# akilli_olcum_cihazi.net
KiCad netlist of a schematic drawn in EAGLE
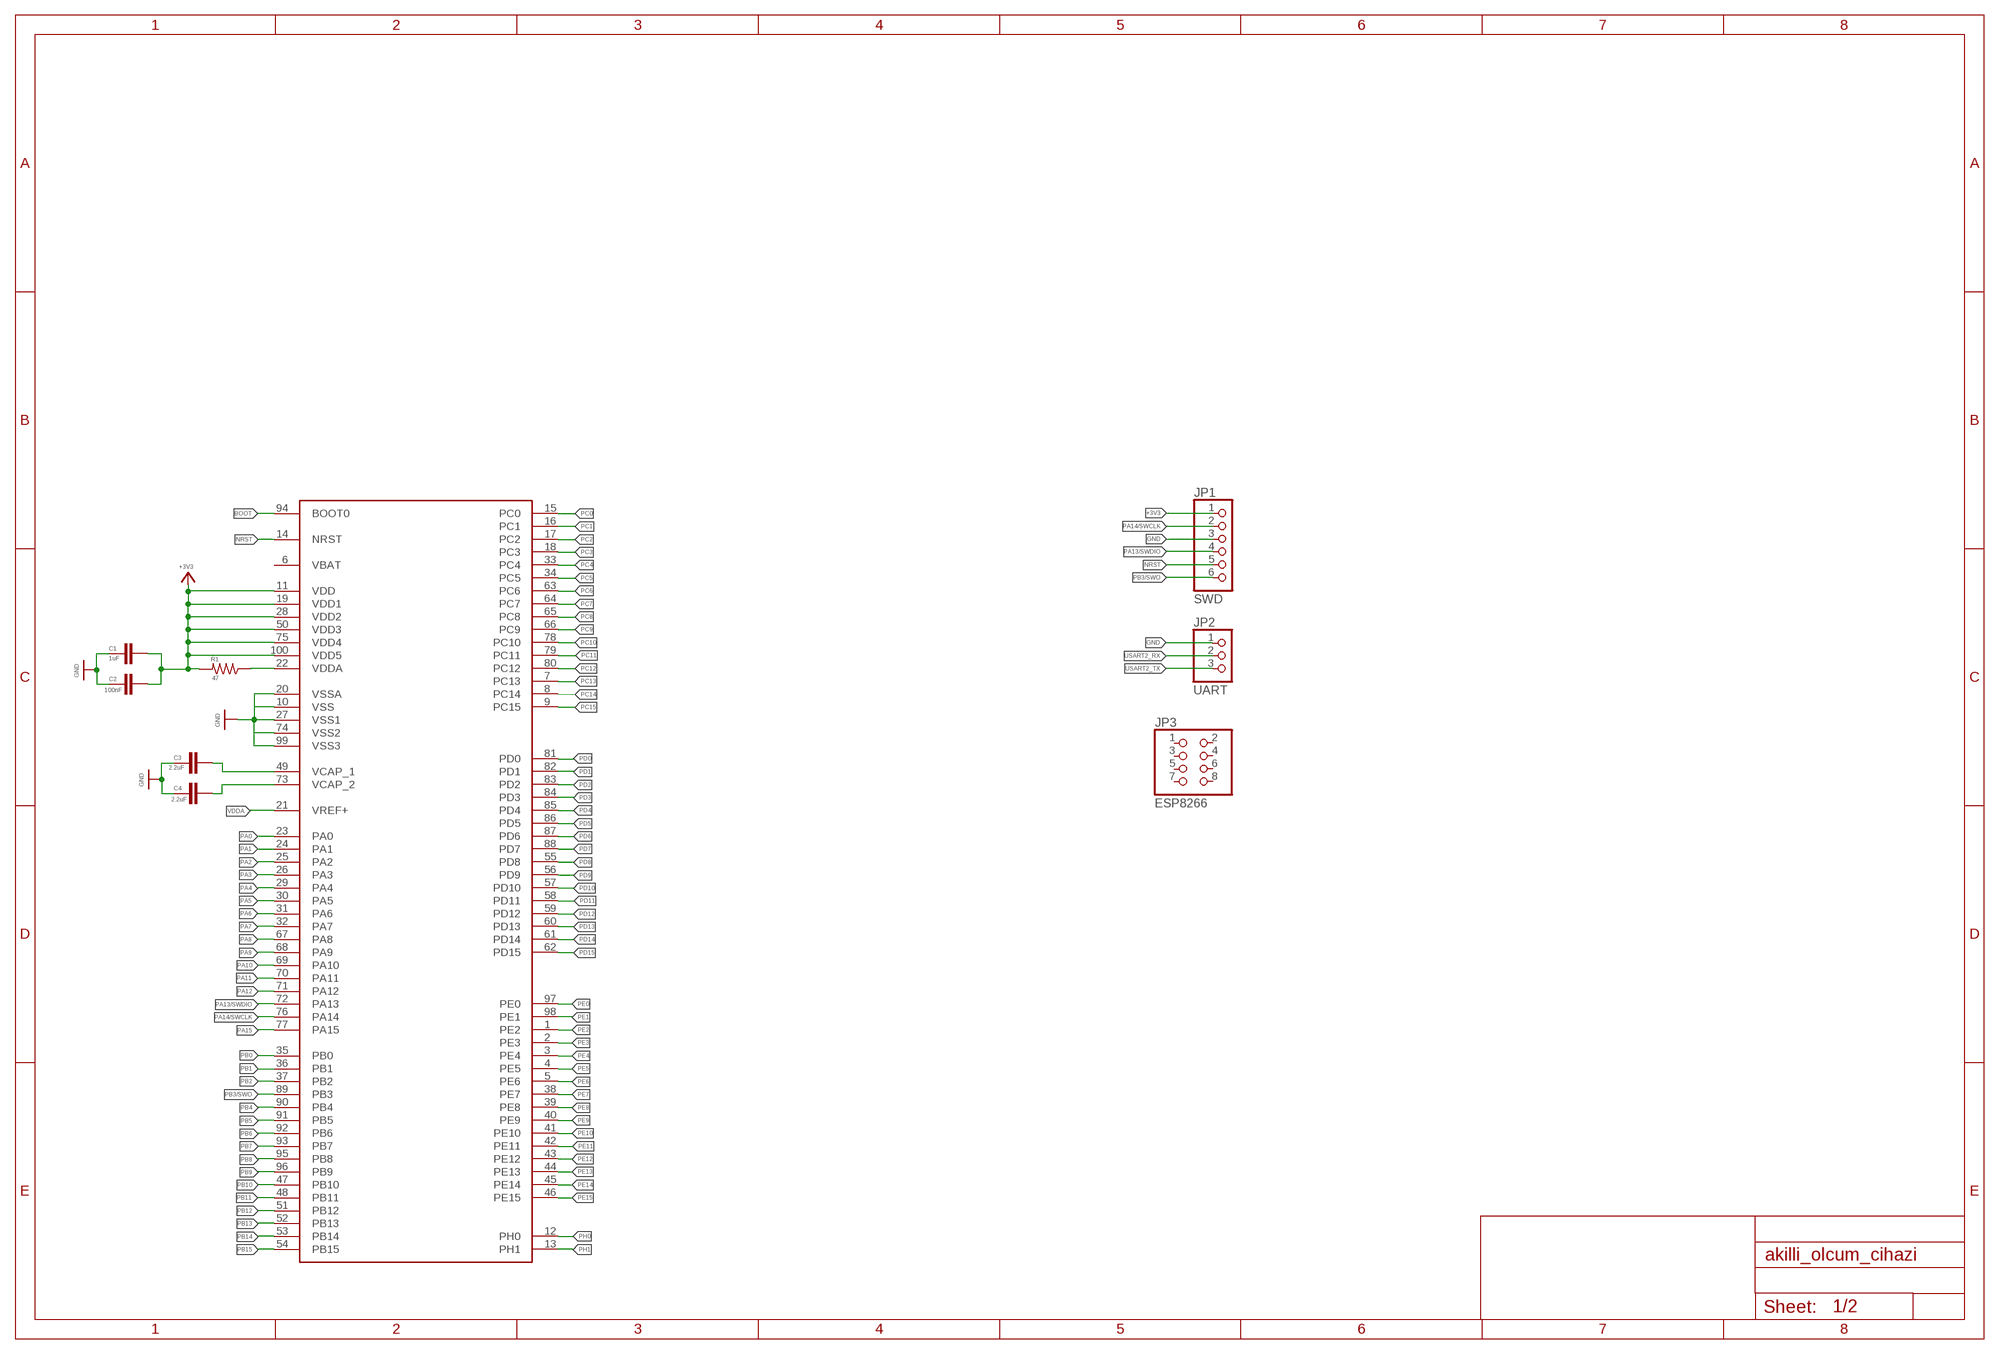
[diagram p0: schematic, sheet 1]
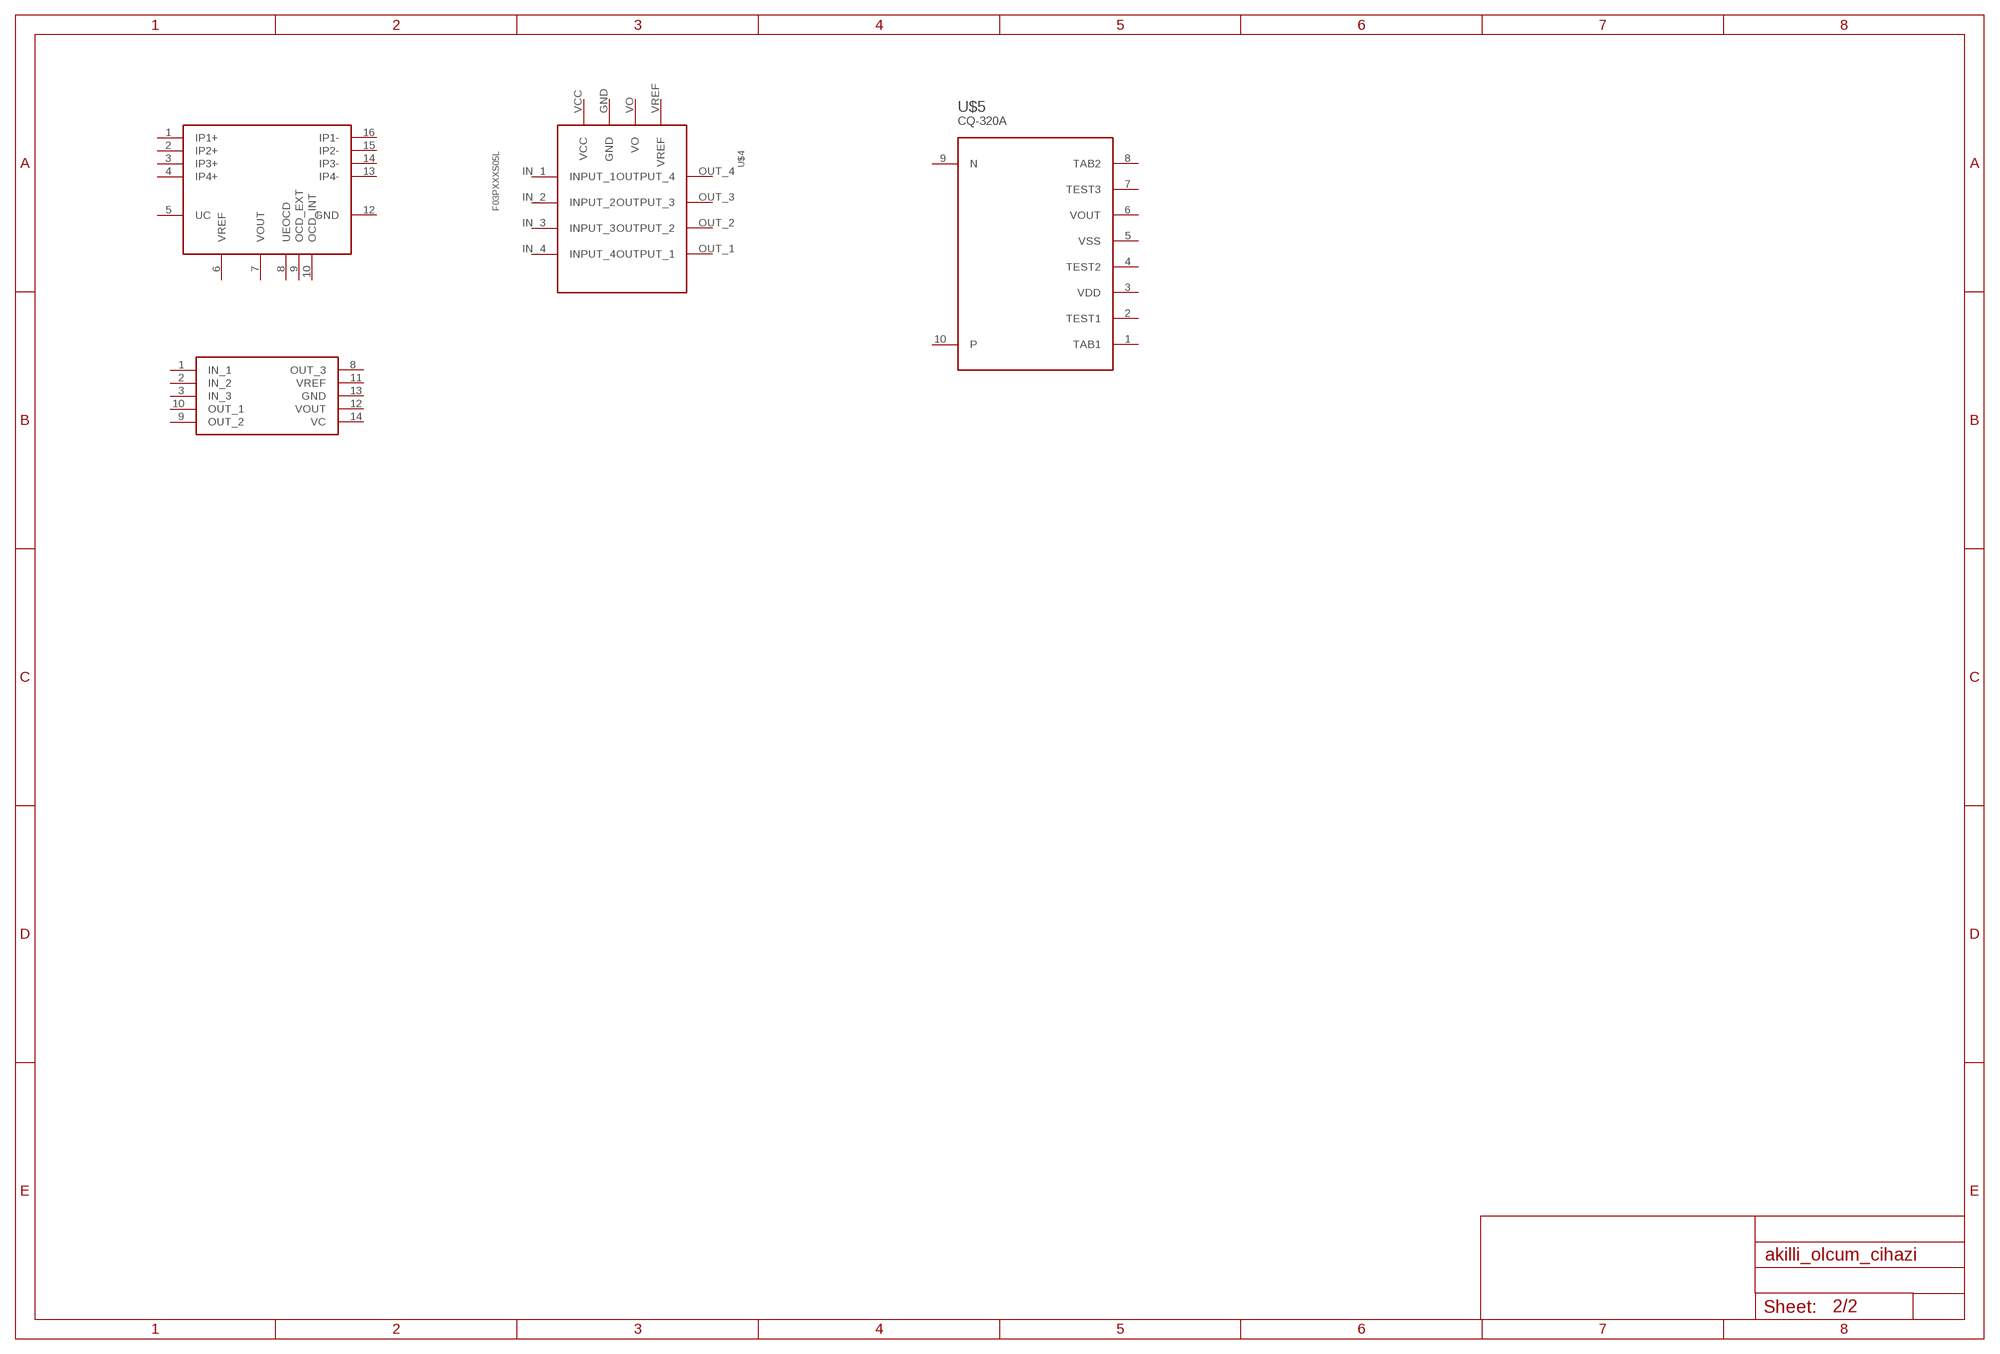
[diagram p1: schematic, sheet 2]

(export (version "E")
  (design (tool "Eeschema 10.0.6"))
  (components
    (comp (ref "C1")
      (value "1uF")
      (footprint "eagle-import:C0805")
      (libsource (lib "eagle-import") (part "C"))
    )
    (comp (ref "C2")
      (value "100nF")
      (footprint "eagle-import:C0805")
      (libsource (lib "eagle-import") (part "C"))
    )
    (comp (ref "C3")
      (value "2.2uF")
      (footprint "eagle-import:C0805")
      (libsource (lib "eagle-import") (part "C"))
    )
    (comp (ref "C4")
      (value "2.2uF")
      (footprint "eagle-import:C0805")
      (libsource (lib "eagle-import") (part "C"))
    )
    (comp (ref "JP1")
      (value "SWD")
      (footprint "eagle-import:1X06")
      (libsource (lib "eagle-import") (part "PINHD-1X6"))
    )
    (comp (ref "JP2")
      (value "UART")
      (footprint "eagle-import:1X03")
      (libsource (lib "eagle-import") (part "PINHD-1X3"))
    )
    (comp (ref "JP3")
      (value "ESP8266")
      (footprint "eagle-import:2X04")
      (libsource (lib "eagle-import") (part "PINHD-2X4"))
    )
    (comp (ref "R1")
      (value "47")
      (footprint "eagle-import:R1206")
      (libsource (lib "eagle-import") (part "R-US_R1206"))
    )
    (comp (ref "U$1")
      (value "STM32F40XSTM32D40X")
      (footprint "eagle-import:LQFP100")
      (libsource (lib "eagle-import") (part "STM32F40XSTM32D40X"))
    )
    (comp (ref "U$2")
      (value "LEM_G02")
      (footprint "eagle-import:LEM_G02")
      (libsource (lib "eagle-import") (part "LEM_G02"))
    )
    (comp (ref "U$3")
      (value "LEM_CASR")
      (footprint "eagle-import:LEM")
      (libsource (lib "eagle-import") (part "LEM_CASR"))
    )
    (comp (ref "U$4")
      (value "F03PXXXS05L")
      (footprint "eagle-import:F03PXXXS05L")
      (libsource (lib "eagle-import") (part "F03PXXXS05L"))
    )
    (comp (ref "U$5")
      (value "CQ-320A")
      (footprint "eagle-import:CQ-320A")
      (libsource (lib "eagle-import") (part "CQ-320A"))
    )
  )
  (nets
    (net (code "1") (name "+3V3") (class "Default")
      (node (ref "C1") (pin "2") (pinfunction "2_2") (pintype "passive"))
      (node (ref "C2") (pin "2") (pinfunction "2_2") (pintype "passive"))
      (node (ref "JP1") (pin "1") (pinfunction "1_1") (pintype "passive"))
      (node (ref "R1") (pin "2") (pinfunction "2_2") (pintype "passive"))
      (node (ref "U$1") (pin "100") (pinfunction "VDD5_100") (pintype "bidirectional"))
      (node (ref "U$1") (pin "11") (pinfunction "VDD_11") (pintype "bidirectional"))
      (node (ref "U$1") (pin "19") (pinfunction "VDD1_19") (pintype "bidirectional"))
      (node (ref "U$1") (pin "28") (pinfunction "VDD2_28") (pintype "bidirectional"))
      (node (ref "U$1") (pin "50") (pinfunction "VDD3_50") (pintype "bidirectional"))
      (node (ref "U$1") (pin "75") (pinfunction "VDD4_75") (pintype "bidirectional"))
    )
    (net (code "2") (name "BOOT") (class "Default")
      (node (ref "U$1") (pin "94") (pinfunction "BOOT0_94") (pintype "bidirectional"))
    )
    (net (code "3") (name "GND") (class "Default")
      (node (ref "C1") (pin "1") (pinfunction "1_1") (pintype "passive"))
      (node (ref "C2") (pin "1") (pinfunction "1_1") (pintype "passive"))
      (node (ref "C3") (pin "1") (pinfunction "1_1") (pintype "passive"))
      (node (ref "C4") (pin "1") (pinfunction "1_1") (pintype "passive"))
      (node (ref "JP1") (pin "3") (pinfunction "3_3") (pintype "passive"))
      (node (ref "JP2") (pin "1") (pinfunction "1_1") (pintype "passive"))
      (node (ref "U$1") (pin "10") (pinfunction "VSS_10") (pintype "bidirectional"))
      (node (ref "U$1") (pin "20") (pinfunction "VSSA_20") (pintype "bidirectional"))
      (node (ref "U$1") (pin "27") (pinfunction "VSS1_27") (pintype "bidirectional"))
      (node (ref "U$1") (pin "74") (pinfunction "VSS2_74") (pintype "bidirectional"))
      (node (ref "U$1") (pin "99") (pinfunction "VSS3_99") (pintype "bidirectional"))
    )
    (net (code "4") (name "NRST") (class "Default")
      (node (ref "JP1") (pin "5") (pinfunction "5_5") (pintype "passive"))
      (node (ref "U$1") (pin "14") (pinfunction "NRST_14") (pintype "bidirectional"))
    )
    (net (code "5") (name "Net-(U$1-VCAP_1)") (class "Default")
      (node (ref "C3") (pin "2") (pinfunction "2_2") (pintype "passive"))
      (node (ref "U$1") (pin "49") (pinfunction "VCAP_1_49") (pintype "bidirectional"))
    )
    (net (code "6") (name "Net-(U$1-VCAP_2)") (class "Default")
      (node (ref "C4") (pin "2") (pinfunction "2_2") (pintype "passive"))
      (node (ref "U$1") (pin "73") (pinfunction "VCAP_2_73") (pintype "bidirectional"))
    )
    (net (code "7") (name "PA0") (class "Default")
      (node (ref "U$1") (pin "23") (pinfunction "PA0_23") (pintype "bidirectional"))
    )
    (net (code "8") (name "PA1") (class "Default")
      (node (ref "U$1") (pin "24") (pinfunction "PA1_24") (pintype "bidirectional"))
    )
    (net (code "9") (name "PA2") (class "Default")
      (node (ref "U$1") (pin "25") (pinfunction "PA2_25") (pintype "bidirectional"))
    )
    (net (code "10") (name "PA3") (class "Default")
      (node (ref "U$1") (pin "26") (pinfunction "PA3_26") (pintype "bidirectional"))
    )
    (net (code "11") (name "PA4") (class "Default")
      (node (ref "U$1") (pin "29") (pinfunction "PA4_29") (pintype "bidirectional"))
    )
    (net (code "12") (name "PA5") (class "Default")
      (node (ref "U$1") (pin "30") (pinfunction "PA5_30") (pintype "bidirectional"))
    )
    (net (code "13") (name "PA6") (class "Default")
      (node (ref "U$1") (pin "31") (pinfunction "PA6_31") (pintype "bidirectional"))
    )
    (net (code "14") (name "PA7") (class "Default")
      (node (ref "U$1") (pin "32") (pinfunction "PA7_32") (pintype "bidirectional"))
    )
    (net (code "15") (name "PA8") (class "Default")
      (node (ref "U$1") (pin "67") (pinfunction "PA8_67") (pintype "bidirectional"))
    )
    (net (code "16") (name "PA9") (class "Default")
      (node (ref "U$1") (pin "68") (pinfunction "PA9_68") (pintype "bidirectional"))
    )
    (net (code "17") (name "PA10") (class "Default")
      (node (ref "U$1") (pin "69") (pinfunction "PA10_69") (pintype "bidirectional"))
    )
    (net (code "18") (name "PA11") (class "Default")
      (node (ref "U$1") (pin "70") (pinfunction "PA11_70") (pintype "bidirectional"))
    )
    (net (code "19") (name "PA12") (class "Default")
      (node (ref "U$1") (pin "71") (pinfunction "PA12_71") (pintype "bidirectional"))
    )
    (net (code "20") (name "PA13{slash}SWDIO") (class "Default")
      (node (ref "JP1") (pin "4") (pinfunction "4_4") (pintype "passive"))
      (node (ref "U$1") (pin "72") (pinfunction "PA13_72") (pintype "bidirectional"))
    )
    (net (code "21") (name "PA14{slash}SWCLK") (class "Default")
      (node (ref "JP1") (pin "2") (pinfunction "2_2") (pintype "passive"))
      (node (ref "U$1") (pin "76") (pinfunction "PA14_76") (pintype "bidirectional"))
    )
    (net (code "22") (name "PA15") (class "Default")
      (node (ref "U$1") (pin "77") (pinfunction "PA15_77") (pintype "bidirectional"))
    )
    (net (code "23") (name "PB0") (class "Default")
      (node (ref "U$1") (pin "35") (pinfunction "PB0_35") (pintype "bidirectional"))
    )
    (net (code "24") (name "PB1") (class "Default")
      (node (ref "U$1") (pin "36") (pinfunction "PB1_36") (pintype "bidirectional"))
    )
    (net (code "25") (name "PB2") (class "Default")
      (node (ref "U$1") (pin "37") (pinfunction "PB2_37") (pintype "bidirectional"))
    )
    (net (code "26") (name "PB3{slash}SWO") (class "Default")
      (node (ref "JP1") (pin "6") (pinfunction "6_6") (pintype "passive"))
      (node (ref "U$1") (pin "89") (pinfunction "PB3_89") (pintype "bidirectional"))
    )
    (net (code "27") (name "PB4") (class "Default")
      (node (ref "U$1") (pin "90") (pinfunction "PB4_90") (pintype "bidirectional"))
    )
    (net (code "28") (name "PB5") (class "Default")
      (node (ref "U$1") (pin "91") (pinfunction "PB5_91") (pintype "bidirectional"))
    )
    (net (code "29") (name "PB6") (class "Default")
      (node (ref "U$1") (pin "92") (pinfunction "PB6_92") (pintype "bidirectional"))
    )
    (net (code "30") (name "PB7") (class "Default")
      (node (ref "U$1") (pin "93") (pinfunction "PB7_93") (pintype "bidirectional"))
    )
    (net (code "31") (name "PB8") (class "Default")
      (node (ref "U$1") (pin "95") (pinfunction "PB8_95") (pintype "bidirectional"))
    )
    (net (code "32") (name "PB9") (class "Default")
      (node (ref "U$1") (pin "96") (pinfunction "PB9_96") (pintype "bidirectional"))
    )
    (net (code "33") (name "PB10") (class "Default")
      (node (ref "U$1") (pin "47") (pinfunction "PB10_47") (pintype "bidirectional"))
    )
    (net (code "34") (name "PB11") (class "Default")
      (node (ref "U$1") (pin "48") (pinfunction "PB11_48") (pintype "bidirectional"))
    )
    (net (code "35") (name "PB12") (class "Default")
      (node (ref "U$1") (pin "51") (pinfunction "PB12_51") (pintype "bidirectional"))
    )
    (net (code "36") (name "PB13") (class "Default")
      (node (ref "U$1") (pin "52") (pinfunction "PB13_52") (pintype "bidirectional"))
    )
    (net (code "37") (name "PB14") (class "Default")
      (node (ref "U$1") (pin "53") (pinfunction "PB14_53") (pintype "bidirectional"))
    )
    (net (code "38") (name "PB15") (class "Default")
      (node (ref "U$1") (pin "54") (pinfunction "PB15_54") (pintype "bidirectional"))
    )
    (net (code "39") (name "PC0") (class "Default")
      (node (ref "U$1") (pin "15") (pinfunction "PC0_15") (pintype "bidirectional"))
    )
    (net (code "40") (name "PC1") (class "Default")
      (node (ref "U$1") (pin "16") (pinfunction "PC1_16") (pintype "bidirectional"))
    )
    (net (code "41") (name "PC2") (class "Default")
      (node (ref "U$1") (pin "17") (pinfunction "PC2_17") (pintype "bidirectional"))
    )
    (net (code "42") (name "PC3") (class "Default")
      (node (ref "U$1") (pin "18") (pinfunction "PC3_18") (pintype "bidirectional"))
    )
    (net (code "43") (name "PC4") (class "Default")
      (node (ref "U$1") (pin "33") (pinfunction "PC4_33") (pintype "bidirectional"))
    )
    (net (code "44") (name "PC5") (class "Default")
      (node (ref "U$1") (pin "34") (pinfunction "PC5_34") (pintype "bidirectional"))
    )
    (net (code "45") (name "PC6") (class "Default")
      (node (ref "U$1") (pin "63") (pinfunction "PC6_63") (pintype "bidirectional"))
    )
    (net (code "46") (name "PC7") (class "Default")
      (node (ref "U$1") (pin "64") (pinfunction "PC7_64") (pintype "bidirectional"))
    )
    (net (code "47") (name "PC8") (class "Default")
      (node (ref "U$1") (pin "65") (pinfunction "PC8_65") (pintype "bidirectional"))
    )
    (net (code "48") (name "PC9") (class "Default")
      (node (ref "U$1") (pin "66") (pinfunction "PC9_66") (pintype "bidirectional"))
    )
    (net (code "49") (name "PC10") (class "Default")
      (node (ref "U$1") (pin "78") (pinfunction "PC10_78") (pintype "bidirectional"))
    )
    (net (code "50") (name "PC11") (class "Default")
      (node (ref "U$1") (pin "79") (pinfunction "PC11_79") (pintype "bidirectional"))
    )
    (net (code "51") (name "PC12") (class "Default")
      (node (ref "U$1") (pin "80") (pinfunction "PC12_80") (pintype "bidirectional"))
    )
    (net (code "52") (name "PC13") (class "Default")
      (node (ref "U$1") (pin "7") (pinfunction "PC13_7") (pintype "bidirectional"))
    )
    (net (code "53") (name "PC14") (class "Default")
      (node (ref "U$1") (pin "8") (pinfunction "PC14_8") (pintype "bidirectional"))
    )
    (net (code "54") (name "PC15") (class "Default")
      (node (ref "U$1") (pin "9") (pinfunction "PC15_9") (pintype "bidirectional"))
    )
    (net (code "55") (name "PD0") (class "Default")
      (node (ref "U$1") (pin "81") (pinfunction "PD0_81") (pintype "bidirectional"))
    )
    (net (code "56") (name "PD1") (class "Default")
      (node (ref "U$1") (pin "82") (pinfunction "PD1_82") (pintype "bidirectional"))
    )
    (net (code "57") (name "PD2") (class "Default")
      (node (ref "U$1") (pin "83") (pinfunction "PD2_83") (pintype "bidirectional"))
    )
    (net (code "58") (name "PD3") (class "Default")
      (node (ref "U$1") (pin "84") (pinfunction "PD3_84") (pintype "bidirectional"))
    )
    (net (code "59") (name "PD4") (class "Default")
      (node (ref "U$1") (pin "85") (pinfunction "PD4_85") (pintype "bidirectional"))
    )
    (net (code "60") (name "PD5") (class "Default")
      (node (ref "U$1") (pin "86") (pinfunction "PD5_86") (pintype "bidirectional"))
    )
    (net (code "61") (name "PD6") (class "Default")
      (node (ref "U$1") (pin "87") (pinfunction "PD6_87") (pintype "bidirectional"))
    )
    (net (code "62") (name "PD7") (class "Default")
      (node (ref "U$1") (pin "88") (pinfunction "PD7_88") (pintype "bidirectional"))
    )
    (net (code "63") (name "PD8") (class "Default")
      (node (ref "U$1") (pin "55") (pinfunction "PD8_55") (pintype "bidirectional"))
    )
    (net (code "64") (name "PD9") (class "Default")
      (node (ref "U$1") (pin "56") (pinfunction "PD9_56") (pintype "bidirectional"))
    )
    (net (code "65") (name "PD10") (class "Default")
      (node (ref "U$1") (pin "57") (pinfunction "PD10_57") (pintype "bidirectional"))
    )
    (net (code "66") (name "PD11") (class "Default")
      (node (ref "U$1") (pin "58") (pinfunction "PD11_58") (pintype "bidirectional"))
    )
    (net (code "67") (name "PD12") (class "Default")
      (node (ref "U$1") (pin "59") (pinfunction "PD12_59") (pintype "bidirectional"))
    )
    (net (code "68") (name "PD13") (class "Default")
      (node (ref "U$1") (pin "60") (pinfunction "PD13_60") (pintype "bidirectional"))
    )
    (net (code "69") (name "PD14") (class "Default")
      (node (ref "U$1") (pin "61") (pinfunction "PD14_61") (pintype "bidirectional"))
    )
    (net (code "70") (name "PD15") (class "Default")
      (node (ref "U$1") (pin "62") (pinfunction "PD15_62") (pintype "bidirectional"))
    )
    (net (code "71") (name "PE0") (class "Default")
      (node (ref "U$1") (pin "97") (pinfunction "PE0_97") (pintype "bidirectional"))
    )
    (net (code "72") (name "PE1") (class "Default")
      (node (ref "U$1") (pin "98") (pinfunction "PE1_98") (pintype "bidirectional"))
    )
    (net (code "73") (name "PE2") (class "Default")
      (node (ref "U$1") (pin "1") (pinfunction "PE2_1") (pintype "bidirectional"))
    )
    (net (code "74") (name "PE3") (class "Default")
      (node (ref "U$1") (pin "2") (pinfunction "PE3_2") (pintype "bidirectional"))
    )
    (net (code "75") (name "PE4") (class "Default")
      (node (ref "U$1") (pin "3") (pinfunction "PE4_3") (pintype "bidirectional"))
    )
    (net (code "76") (name "PE5") (class "Default")
      (node (ref "U$1") (pin "4") (pinfunction "PE5_4") (pintype "bidirectional"))
    )
    (net (code "77") (name "PE6") (class "Default")
      (node (ref "U$1") (pin "5") (pinfunction "PE6_5") (pintype "bidirectional"))
    )
    (net (code "78") (name "PE7") (class "Default")
      (node (ref "U$1") (pin "38") (pinfunction "PE7_38") (pintype "bidirectional"))
    )
    (net (code "79") (name "PE8") (class "Default")
      (node (ref "U$1") (pin "39") (pinfunction "PE8_39") (pintype "bidirectional"))
    )
    (net (code "80") (name "PE9") (class "Default")
      (node (ref "U$1") (pin "40") (pinfunction "PE9_40") (pintype "bidirectional"))
    )
    (net (code "81") (name "PE10") (class "Default")
      (node (ref "U$1") (pin "41") (pinfunction "PE10_41") (pintype "bidirectional"))
    )
    (net (code "82") (name "PE11") (class "Default")
      (node (ref "U$1") (pin "42") (pinfunction "PE11_42") (pintype "bidirectional"))
    )
    (net (code "83") (name "PE12") (class "Default")
      (node (ref "U$1") (pin "43") (pinfunction "PE12_43") (pintype "bidirectional"))
    )
    (net (code "84") (name "PE13") (class "Default")
      (node (ref "U$1") (pin "44") (pinfunction "PE13_44") (pintype "bidirectional"))
    )
    (net (code "85") (name "PE14") (class "Default")
      (node (ref "U$1") (pin "45") (pinfunction "PE14_45") (pintype "bidirectional"))
    )
    (net (code "86") (name "PE15") (class "Default")
      (node (ref "U$1") (pin "46") (pinfunction "PE15_46") (pintype "bidirectional"))
    )
    (net (code "87") (name "PH0") (class "Default")
      (node (ref "U$1") (pin "12") (pinfunction "PH0_12") (pintype "bidirectional"))
    )
    (net (code "88") (name "PH1") (class "Default")
      (node (ref "U$1") (pin "13") (pinfunction "PH1_13") (pintype "bidirectional"))
    )
    (net (code "89") (name "USART2_RX") (class "Default")
      (node (ref "JP2") (pin "2") (pinfunction "2_2") (pintype "passive"))
    )
    (net (code "90") (name "USART2_TX") (class "Default")
      (node (ref "JP2") (pin "3") (pinfunction "3_3") (pintype "passive"))
    )
    (net (code "91") (name "VDDA") (class "Default")
      (node (ref "R1") (pin "1") (pinfunction "1_1") (pintype "passive"))
      (node (ref "U$1") (pin "21") (pinfunction "VREF+_21") (pintype "bidirectional"))
      (node (ref "U$1") (pin "22") (pinfunction "VDDA_22") (pintype "bidirectional"))
    )
    (net (code "92") (name "unconnected-(JP3-Pad1)") (class "Default")
      (node (ref "JP3") (pin "1") (pinfunction "1_1") (pintype "passive"))
    )
    (net (code "93") (name "unconnected-(JP3-Pad2)") (class "Default")
      (node (ref "JP3") (pin "2") (pinfunction "2_2") (pintype "passive"))
    )
    (net (code "94") (name "unconnected-(JP3-Pad3)") (class "Default")
      (node (ref "JP3") (pin "3") (pinfunction "3_3") (pintype "passive"))
    )
    (net (code "95") (name "unconnected-(JP3-Pad4)") (class "Default")
      (node (ref "JP3") (pin "4") (pinfunction "4_4") (pintype "passive"))
    )
    (net (code "96") (name "unconnected-(JP3-Pad5)") (class "Default")
      (node (ref "JP3") (pin "5") (pinfunction "5_5") (pintype "passive"))
    )
    (net (code "97") (name "unconnected-(JP3-Pad6)") (class "Default")
      (node (ref "JP3") (pin "6") (pinfunction "6_6") (pintype "passive"))
    )
    (net (code "98") (name "unconnected-(JP3-Pad7)") (class "Default")
      (node (ref "JP3") (pin "7") (pinfunction "7_7") (pintype "passive"))
    )
    (net (code "99") (name "unconnected-(JP3-Pad8)") (class "Default")
      (node (ref "JP3") (pin "8") (pinfunction "8_8") (pintype "passive"))
    )
    (net (code "100") (name "unconnected-(U$1-VBAT-Pad6)") (class "Default")
      (node (ref "U$1") (pin "6") (pinfunction "VBAT_6") (pintype "bidirectional"))
    )
    (net (code "101") (name "unconnected-(U$2-GND-Pad12)") (class "Default")
      (node (ref "U$2") (pin "12") (pinfunction "GND_12") (pintype "bidirectional"))
    )
    (net (code "102") (name "unconnected-(U$2-IP1+-Pad1)") (class "Default")
      (node (ref "U$2") (pin "1") (pinfunction "IP1+_1") (pintype "bidirectional"))
    )
    (net (code "103") (name "unconnected-(U$2-IP1--Pad16)") (class "Default")
      (node (ref "U$2") (pin "16") (pinfunction "IP1-_16") (pintype "bidirectional"))
    )
    (net (code "104") (name "unconnected-(U$2-IP2+-Pad2)") (class "Default")
      (node (ref "U$2") (pin "2") (pinfunction "IP2+_2") (pintype "bidirectional"))
    )
    (net (code "105") (name "unconnected-(U$2-IP2--Pad15)") (class "Default")
      (node (ref "U$2") (pin "15") (pinfunction "IP2-_15") (pintype "bidirectional"))
    )
    (net (code "106") (name "unconnected-(U$2-IP3+-Pad3)") (class "Default")
      (node (ref "U$2") (pin "3") (pinfunction "IP3+_3") (pintype "bidirectional"))
    )
    (net (code "107") (name "unconnected-(U$2-IP3--Pad14)") (class "Default")
      (node (ref "U$2") (pin "14") (pinfunction "IP3-_14") (pintype "bidirectional"))
    )
    (net (code "108") (name "unconnected-(U$2-IP4+-Pad4)") (class "Default")
      (node (ref "U$2") (pin "4") (pinfunction "IP4+_4") (pintype "bidirectional"))
    )
    (net (code "109") (name "unconnected-(U$2-IP4--Pad13)") (class "Default")
      (node (ref "U$2") (pin "13") (pinfunction "IP4-_13") (pintype "bidirectional"))
    )
    (net (code "110") (name "unconnected-(U$2-OCD_EXT-Pad9)") (class "Default")
      (node (ref "U$2") (pin "9") (pinfunction "OCD_EXT_9") (pintype "bidirectional"))
    )
    (net (code "111") (name "unconnected-(U$2-OCD_INT-Pad10)") (class "Default")
      (node (ref "U$2") (pin "10") (pinfunction "OCD_INT_10") (pintype "bidirectional"))
    )
    (net (code "112") (name "unconnected-(U$2-UC-Pad5)") (class "Default")
      (node (ref "U$2") (pin "5") (pinfunction "UC_5") (pintype "bidirectional"))
    )
    (net (code "113") (name "unconnected-(U$2-UEOCD-Pad8)") (class "Default")
      (node (ref "U$2") (pin "8") (pinfunction "UEOCD_8") (pintype "bidirectional"))
    )
    (net (code "114") (name "unconnected-(U$2-VOUT-Pad7)") (class "Default")
      (node (ref "U$2") (pin "7") (pinfunction "VOUT_7") (pintype "bidirectional"))
    )
    (net (code "115") (name "unconnected-(U$2-VREF-Pad6)") (class "Default")
      (node (ref "U$2") (pin "6") (pinfunction "VREF_6") (pintype "bidirectional"))
    )
    (net (code "116") (name "unconnected-(U$3-GND-Pad13)") (class "Default")
      (node (ref "U$3") (pin "13") (pinfunction "GND_13") (pintype "bidirectional"))
    )
    (net (code "117") (name "unconnected-(U$3-IN_1-Pad1)") (class "Default")
      (node (ref "U$3") (pin "1") (pinfunction "IN_1_1") (pintype "bidirectional"))
    )
    (net (code "118") (name "unconnected-(U$3-IN_2-Pad2)") (class "Default")
      (node (ref "U$3") (pin "2") (pinfunction "IN_2_2") (pintype "bidirectional"))
    )
    (net (code "119") (name "unconnected-(U$3-IN_3-Pad3)") (class "Default")
      (node (ref "U$3") (pin "3") (pinfunction "IN_3_3") (pintype "bidirectional"))
    )
    (net (code "120") (name "unconnected-(U$3-OUT_1-Pad10)") (class "Default")
      (node (ref "U$3") (pin "10") (pinfunction "OUT_1_10") (pintype "bidirectional"))
    )
    (net (code "121") (name "unconnected-(U$3-OUT_2-Pad9)") (class "Default")
      (node (ref "U$3") (pin "9") (pinfunction "OUT_2_9") (pintype "bidirectional"))
    )
    (net (code "122") (name "unconnected-(U$3-OUT_3-Pad8)") (class "Default")
      (node (ref "U$3") (pin "8") (pinfunction "OUT_3_8") (pintype "bidirectional"))
    )
    (net (code "123") (name "unconnected-(U$3-VC-Pad14)") (class "Default")
      (node (ref "U$3") (pin "14") (pinfunction "VC_14") (pintype "bidirectional"))
    )
    (net (code "124") (name "unconnected-(U$3-VOUT-Pad12)") (class "Default")
      (node (ref "U$3") (pin "12") (pinfunction "VOUT_12") (pintype "bidirectional"))
    )
    (net (code "125") (name "unconnected-(U$3-VREF-Pad11)") (class "Default")
      (node (ref "U$3") (pin "11") (pinfunction "VREF_11") (pintype "bidirectional"))
    )
    (net (code "126") (name "unconnected-(U$4-INPUT_1-PadIN_1)") (class "Default")
      (node (ref "U$4") (pin "IN_1") (pinfunction "INPUT_1_IN_1") (pintype "bidirectional"))
    )
    (net (code "127") (name "unconnected-(U$4-INPUT_2-PadIN_2)") (class "Default")
      (node (ref "U$4") (pin "IN_2") (pinfunction "INPUT_2_IN_2") (pintype "bidirectional"))
    )
    (net (code "128") (name "unconnected-(U$4-INPUT_3-PadIN_3)") (class "Default")
      (node (ref "U$4") (pin "IN_3") (pinfunction "INPUT_3_IN_3") (pintype "bidirectional"))
    )
    (net (code "129") (name "unconnected-(U$4-INPUT_4-PadIN_4)") (class "Default")
      (node (ref "U$4") (pin "IN_4") (pinfunction "INPUT_4_IN_4") (pintype "bidirectional"))
    )
    (net (code "130") (name "unconnected-(U$4-OUTPUT_1-PadOUT_1)") (class "Default")
      (node (ref "U$4") (pin "OUT_1") (pinfunction "OUTPUT_1_OUT_1") (pintype "bidirectional"))
    )
    (net (code "131") (name "unconnected-(U$4-OUTPUT_2-PadOUT_2)") (class "Default")
      (node (ref "U$4") (pin "OUT_2") (pinfunction "OUTPUT_2_OUT_2") (pintype "bidirectional"))
    )
    (net (code "132") (name "unconnected-(U$4-OUTPUT_3-PadOUT_3)") (class "Default")
      (node (ref "U$4") (pin "OUT_3") (pinfunction "OUTPUT_3_OUT_3") (pintype "bidirectional"))
    )
    (net (code "133") (name "unconnected-(U$4-OUTPUT_4-PadOUT_4)") (class "Default")
      (node (ref "U$4") (pin "OUT_4") (pinfunction "OUTPUT_4_OUT_4") (pintype "bidirectional"))
    )
    (net (code "134") (name "unconnected-(U$4-PadGND)") (class "Default")
      (node (ref "U$4") (pin "GND") (pinfunction "GND_GND") (pintype "bidirectional"))
    )
    (net (code "135") (name "unconnected-(U$4-PadVCC)") (class "Default")
      (node (ref "U$4") (pin "VCC") (pinfunction "VCC_VCC") (pintype "bidirectional"))
    )
    (net (code "136") (name "unconnected-(U$4-PadVO)") (class "Default")
      (node (ref "U$4") (pin "VO") (pinfunction "VO_VO") (pintype "bidirectional"))
    )
    (net (code "137") (name "unconnected-(U$4-PadVREF)") (class "Default")
      (node (ref "U$4") (pin "VREF") (pinfunction "VREF_VREF") (pintype "bidirectional"))
    )
    (net (code "138") (name "unconnected-(U$5-N-Pad9)") (class "Default")
      (node (ref "U$5") (pin "9") (pinfunction "N_9") (pintype "bidirectional"))
    )
    (net (code "139") (name "unconnected-(U$5-P-Pad10)") (class "Default")
      (node (ref "U$5") (pin "10") (pinfunction "P_10") (pintype "bidirectional"))
    )
    (net (code "140") (name "unconnected-(U$5-TAB1-Pad1)") (class "Default")
      (node (ref "U$5") (pin "1") (pinfunction "TAB1_1") (pintype "bidirectional"))
    )
    (net (code "141") (name "unconnected-(U$5-TAB2-Pad8)") (class "Default")
      (node (ref "U$5") (pin "8") (pinfunction "TAB2_8") (pintype "bidirectional"))
    )
    (net (code "142") (name "unconnected-(U$5-TEST1-Pad2)") (class "Default")
      (node (ref "U$5") (pin "2") (pinfunction "TEST1_2") (pintype "bidirectional"))
    )
    (net (code "143") (name "unconnected-(U$5-TEST2-Pad4)") (class "Default")
      (node (ref "U$5") (pin "4") (pinfunction "TEST2_4") (pintype "bidirectional"))
    )
    (net (code "144") (name "unconnected-(U$5-TEST3-Pad7)") (class "Default")
      (node (ref "U$5") (pin "7") (pinfunction "TEST3_7") (pintype "bidirectional"))
    )
    (net (code "145") (name "unconnected-(U$5-VDD-Pad3)") (class "Default")
      (node (ref "U$5") (pin "3") (pinfunction "VDD_3") (pintype "bidirectional"))
    )
    (net (code "146") (name "unconnected-(U$5-VOUT-Pad6)") (class "Default")
      (node (ref "U$5") (pin "6") (pinfunction "VOUT_6") (pintype "bidirectional"))
    )
    (net (code "147") (name "unconnected-(U$5-VSS-Pad5)") (class "Default")
      (node (ref "U$5") (pin "5") (pinfunction "VSS_5") (pintype "bidirectional"))
    )
  )
)
